# Sheet1.net
KiCad netlist of a schematic drawn in Altium Designer
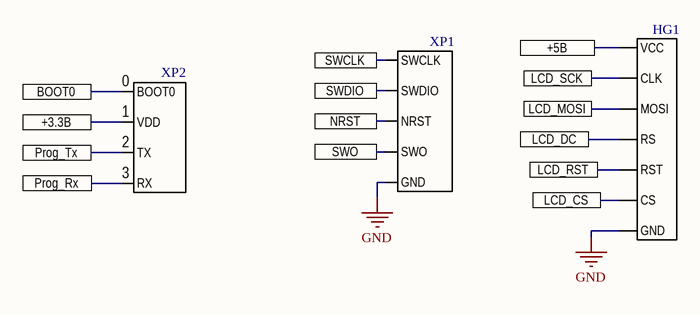
[diagram p0: Sheet1.SchDoc]

(export (version "E")
  (design (tool "Eeschema 10.0.6"))
  (components
    (comp (ref "HG1")
      (value "TFT_SPI")
      (footprint "LCD_TFT_SPI")
      (libsource (lib "Schlib2") (part "TFT_SPI"))
    )
    (comp (ref "XP1") (value "SWD") (footprint "SWD") (libsource (lib "Schlib2") (part "SWD")))
    (comp (ref "XP2") (value "UART") (footprint "UART") (libsource (lib "Schlib2") (part "UART")))
  )
  (nets
    (net (code "1") (name "/+3.3В") (class "Default")
      (node (ref "XP2") (pin "1") (pinfunction "VDD_1") (pintype "passive"))
    )
    (net (code "2") (name "/+5В") (class "Default")
      (node (ref "HG1") (pin "1") (pinfunction "VCC_1") (pintype "passive"))
    )
    (net (code "3") (name "/BOOT0") (class "Default")
      (node (ref "XP2") (pin "0") (pinfunction "BOOT0_0") (pintype "passive"))
    )
    (net (code "4") (name "/LCD_CS") (class "Default")
      (node (ref "HG1") (pin "7") (pinfunction "CS_7") (pintype "passive"))
    )
    (net (code "5") (name "/LCD_DC") (class "Default")
      (node (ref "HG1") (pin "5") (pinfunction "RS_5") (pintype "passive"))
    )
    (net (code "6") (name "/LCD_MOSI") (class "Default")
      (node (ref "HG1") (pin "4") (pinfunction "MOSI_4") (pintype "passive"))
    )
    (net (code "7") (name "/LCD_RST") (class "Default")
      (node (ref "HG1") (pin "6") (pinfunction "RST_6") (pintype "passive"))
    )
    (net (code "8") (name "/LCD_SCK") (class "Default")
      (node (ref "HG1") (pin "3") (pinfunction "CLK_3") (pintype "passive"))
    )
    (net (code "9") (name "/NRST") (class "Default")
      (node (ref "XP1") (pin "3") (pinfunction "NRST_3") (pintype "passive"))
    )
    (net (code "10") (name "/Prog_Rx") (class "Default")
      (node (ref "XP2") (pin "3") (pinfunction "RX_3") (pintype "passive"))
    )
    (net (code "11") (name "/Prog_Tx") (class "Default")
      (node (ref "XP2") (pin "2") (pinfunction "TX_2") (pintype "passive"))
    )
    (net (code "12") (name "/SWCLK") (class "Default")
      (node (ref "XP1") (pin "0") (pinfunction "SWCLK_0") (pintype "passive"))
    )
    (net (code "13") (name "/SWDIO") (class "Default")
      (node (ref "XP1") (pin "2") (pinfunction "SWDIO_2") (pintype "passive"))
    )
    (net (code "14") (name "/SWO") (class "Default")
      (node (ref "XP1") (pin "4") (pinfunction "SWO_4") (pintype "passive"))
    )
    (net (code "15") (name "GND") (class "Default")
      (node (ref "HG1") (pin "2") (pinfunction "GND_2") (pintype "passive"))
      (node (ref "XP1") (pin "1") (pinfunction "GND_1") (pintype "passive"))
    )
  )
)
